# ADC_Block.net
KiCad netlist of a schematic drawn in EAGLE
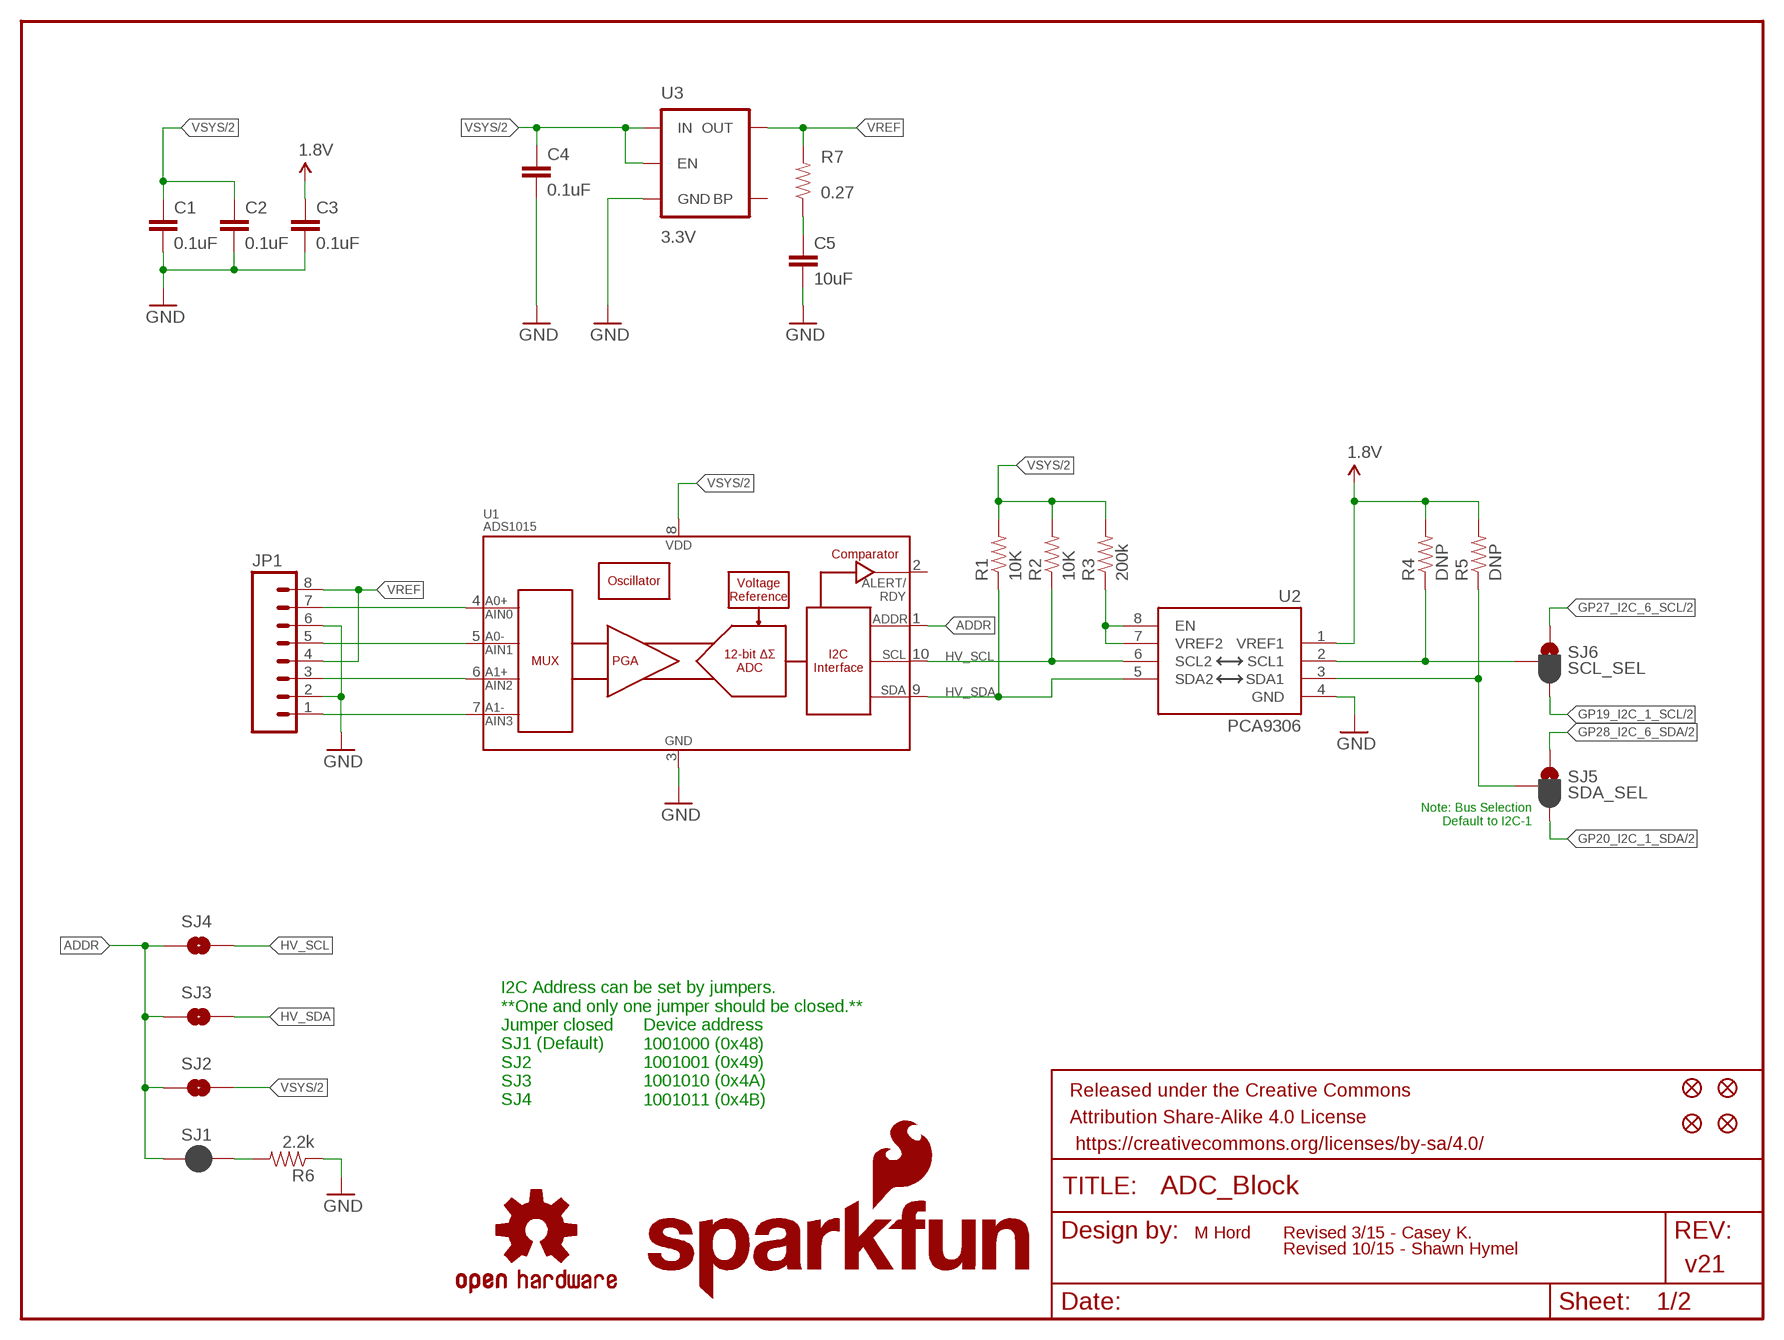
[diagram p0: schematic, sheet 1]
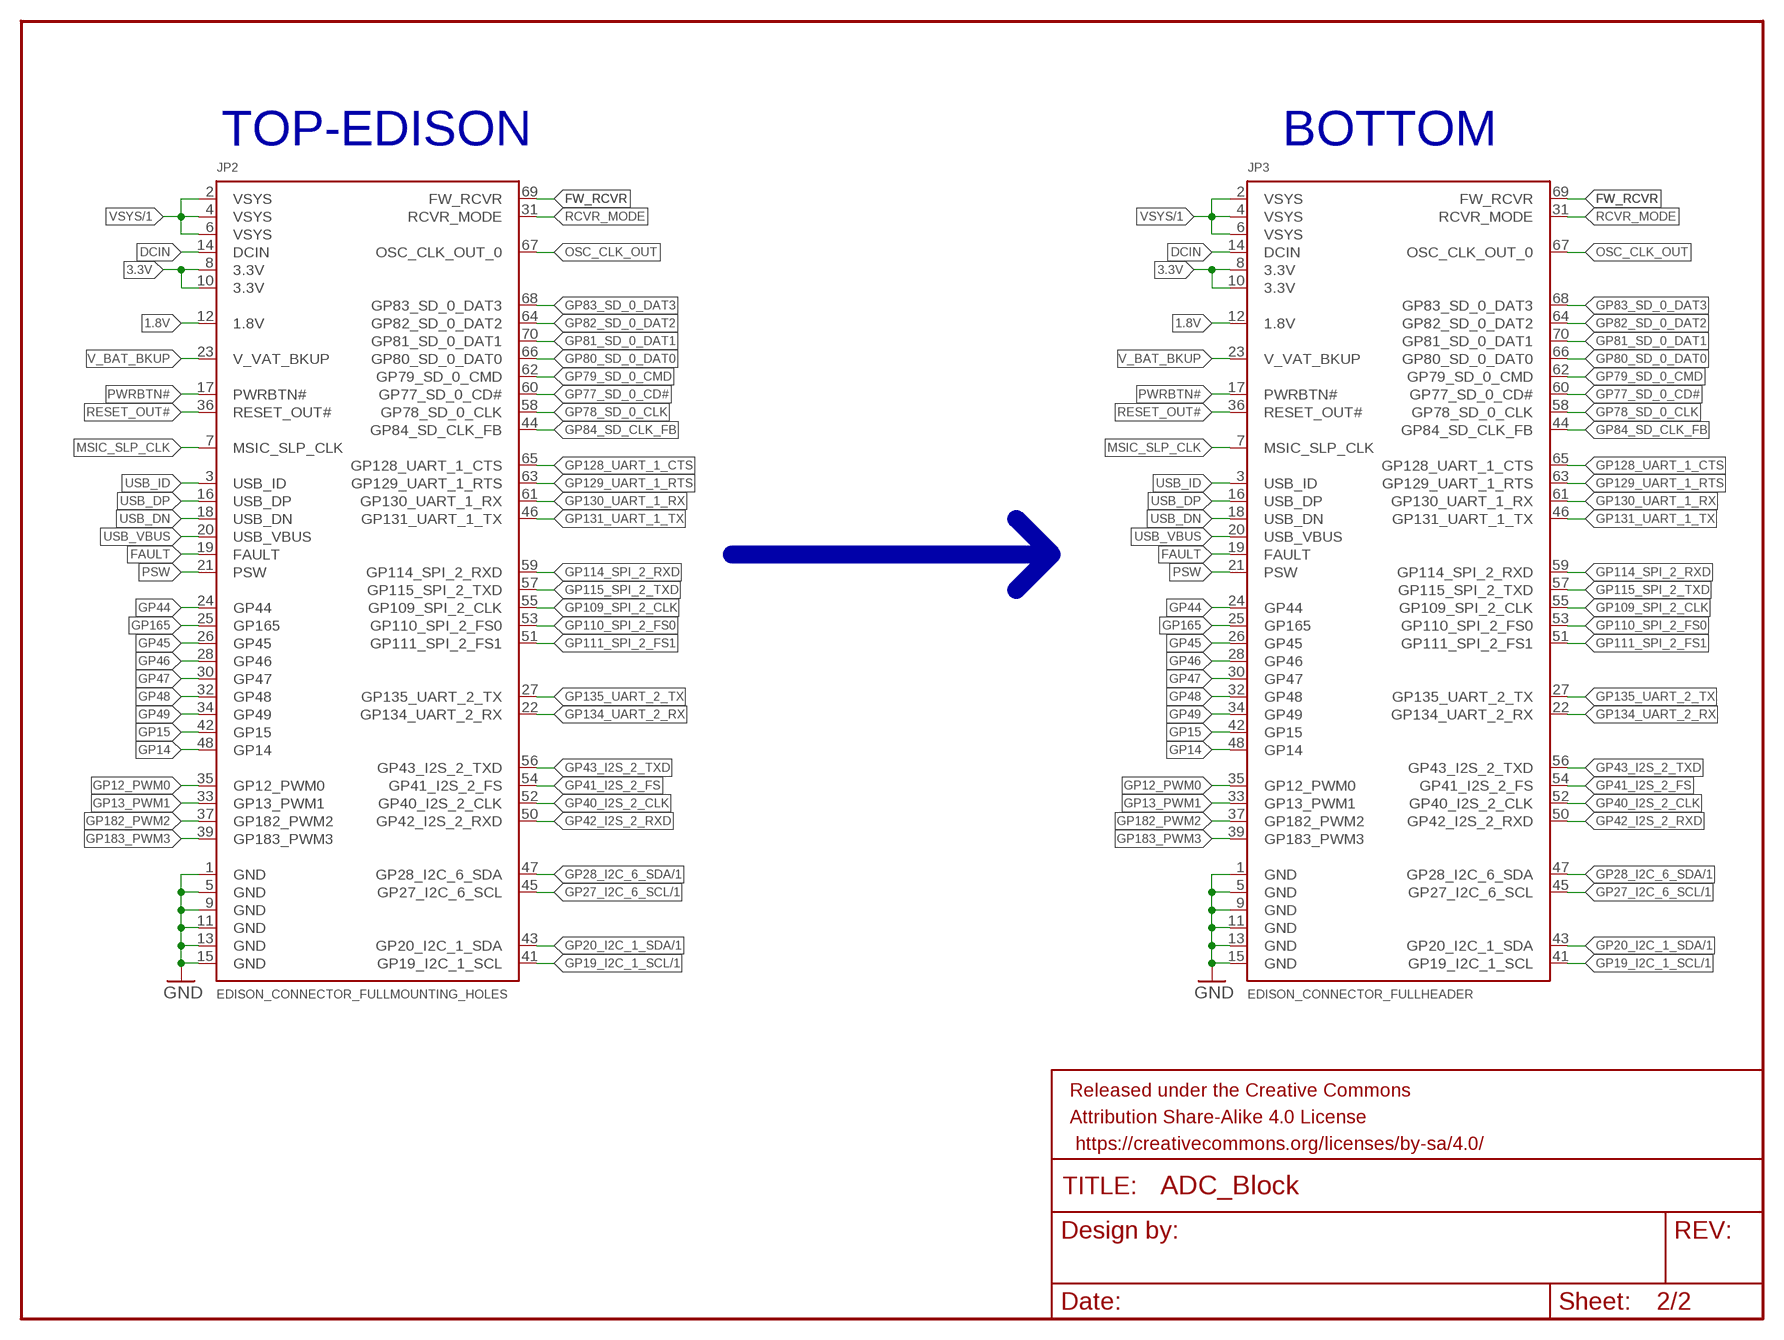
[diagram p1: schematic, sheet 2]

(export (version "E")
  (design (tool "Eeschema 10.0.6"))
  (components
    (comp (ref "C1")
      (value "0.1uF")
      (footprint "eagle-import:0603-CAP")
      (libsource (lib "eagle-import") (part "0.1UF-25V(+80/-20%)(0603)"))
    )
    (comp (ref "C2")
      (value "0.1uF")
      (footprint "eagle-import:0603-CAP")
      (libsource (lib "eagle-import") (part "0.1UF-25V(+80/-20%)(0603)"))
    )
    (comp (ref "C3")
      (value "0.1uF")
      (footprint "eagle-import:0603-CAP")
      (libsource (lib "eagle-import") (part "0.1UF-25V(+80/-20%)(0603)"))
    )
    (comp (ref "C4")
      (value "0.1uF")
      (footprint "eagle-import:0603-CAP")
      (libsource (lib "eagle-import") (part "0.1UF-25V(+80/-20%)(0603)"))
    )
    (comp (ref "C5")
      (value "10uF")
      (footprint "eagle-import:0805-CAP")
      (libsource (lib "eagle-import") (part "10UF10V10%(0805)"))
    )
    (comp (ref "FID1")
      (value "FIDUCIAL1X2")
      (footprint "eagle-import:FIDUCIAL-1X2")
      (libsource (lib "eagle-import") (part "FIDUCIAL1X2"))
    )
    (comp (ref "FID2")
      (value "FIDUCIAL1X2")
      (footprint "eagle-import:FIDUCIAL-1X2")
      (libsource (lib "eagle-import") (part "FIDUCIAL1X2"))
    )
    (comp (ref "FID3")
      (value "FIDUCIAL1X2")
      (footprint "eagle-import:FIDUCIAL-1X2")
      (libsource (lib "eagle-import") (part "FIDUCIAL1X2"))
    )
    (comp (ref "FID4")
      (value "FIDUCIAL1X2")
      (footprint "eagle-import:FIDUCIAL-1X2")
      (libsource (lib "eagle-import") (part "FIDUCIAL1X2"))
    )
    (comp (ref "FRAME1")
      (value "FRAME-LETTER")
      (footprint "eagle-import:CREATIVE_COMMONS")
      (libsource (lib "eagle-import") (part "FRAME-LETTER"))
    )
    (comp (ref "JP1")
      (value "M08LOCK")
      (footprint "eagle-import:1X08_LOCK")
      (libsource (lib "eagle-import") (part "M08LOCK"))
    )
    (comp (ref "LOGO1")
      (value "SFE_LOGO_NAME_FLAME.1_INCH")
      (footprint "eagle-import:SFE_LOGO_NAME_FLAME_.1")
      (libsource (lib "eagle-import") (part "SFE_LOGO_NAME_FLAME.1_INCH"))
    )
    (comp (ref "LOGO2")
      (value "OSHW-LOGOS")
      (footprint "eagle-import:OSHW-LOGO-S")
      (libsource (lib "eagle-import") (part "OSHW-LOGOS"))
    )
    (comp (ref "LOGO3")
      (value "SFE_LOGO_NAME_FLAME.1_INCH")
      (footprint "eagle-import:SFE_LOGO_NAME_FLAME_.1")
      (libsource (lib "eagle-import") (part "SFE_LOGO_NAME_FLAME.1_INCH"))
    )
    (comp (ref "LOGO4")
      (value "OSHW-LOGOS")
      (footprint "eagle-import:OSHW-LOGO-S")
      (libsource (lib "eagle-import") (part "OSHW-LOGOS"))
    )
    (comp (ref "R1")
      (value "10K")
      (footprint "eagle-import:0603-RES")
      (libsource (lib "eagle-import") (part "10KOHM-1/10W-1%(0603)0603"))
    )
    (comp (ref "R2")
      (value "10K")
      (footprint "eagle-import:0603-RES")
      (libsource (lib "eagle-import") (part "10KOHM-1/10W-1%(0603)0603"))
    )
    (comp (ref "R3")
      (value "200k")
      (footprint "eagle-import:0603-RES")
      (libsource (lib "eagle-import") (part "200KOHM1/10W1%(0603)200K"))
    )
    (comp (ref "R4")
      (value "DNP")
      (footprint "eagle-import:0603-RES")
      (libsource (lib "eagle-import") (part "2.2KOHM-1/10W-1%(0603)"))
    )
    (comp (ref "R5")
      (value "DNP")
      (footprint "eagle-import:0603-RES")
      (libsource (lib "eagle-import") (part "2.2KOHM-1/10W-1%(0603)"))
    )
    (comp (ref "R6")
      (value "2.2k")
      (footprint "eagle-import:0603-RES")
      (libsource (lib "eagle-import") (part "2.2KOHM-1/10W-1%(0603)"))
    )
    (comp (ref "R7")
      (value "0.27")
      (footprint "eagle-import:0603-RES")
      (libsource (lib "eagle-import") (part "0.27OHM-1/10W-1%(0603)"))
    )
    (comp (ref "SJ1")
      (value "JUMPER-PAD-2-NC_BY_PASTE")
      (footprint "eagle-import:PAD-JUMPER-2-NC_BY_PASTE_YES_SILK")
      (libsource (lib "eagle-import") (part "JUMPER-PAD-2-NC_BY_PASTE"))
    )
    (comp (ref "SJ2")
      (value "JUMPER-PAD-2-NOYES_SILK")
      (footprint "eagle-import:PAD-JUMPER-2-NO_YES_SILK")
      (libsource (lib "eagle-import") (part "JUMPER-PAD-2-NOYES_SILK"))
    )
    (comp (ref "SJ3")
      (value "JUMPER-PAD-2-NOYES_SILK")
      (footprint "eagle-import:PAD-JUMPER-2-NO_YES_SILK")
      (libsource (lib "eagle-import") (part "JUMPER-PAD-2-NOYES_SILK"))
    )
    (comp (ref "SJ4")
      (value "JUMPER-PAD-2-NOYES_SILK")
      (footprint "eagle-import:PAD-JUMPER-2-NO_YES_SILK")
      (libsource (lib "eagle-import") (part "JUMPER-PAD-2-NOYES_SILK"))
    )
    (comp (ref "SJ5")
      (value "SDA_SEL")
      (footprint "eagle-import:PAD-JUMPER-3-2OF3_NC_BY_PASTE_YES_SILK_FULL_BOX")
      (libsource (lib "eagle-import") (part "JUMPER-PAD-3-2OF3_NC_BY_PASTE"))
    )
    (comp (ref "SJ6")
      (value "SCL_SEL")
      (footprint "eagle-import:PAD-JUMPER-3-2OF3_NC_BY_PASTE_YES_SILK_FULL_BOX")
      (libsource (lib "eagle-import") (part "JUMPER-PAD-3-2OF3_NC_BY_PASTE"))
    )
    (comp (ref "U1")
      (value "ADS1015")
      (footprint "eagle-import:MSOP10")
      (libsource (lib "eagle-import") (part "ADS1015"))
    )
    (comp (ref "U2")
      (value "PCA9306")
      (footprint "eagle-import:PCA9306DC-1_1")
      (libsource (lib "eagle-import") (part "PCA9306PCA9306DC-1{colon}1"))
    )
    (comp (ref "U3")
      (value "3.3V")
      (footprint "eagle-import:SOT23-5")
      (libsource (lib "eagle-import") (part "MIC52053.3V"))
    )
    (comp (ref "FRAME2")
      (value "FRAME-LETTER")
      (footprint "eagle-import:CREATIVE_COMMONS")
      (libsource (lib "eagle-import") (part "FRAME-LETTER"))
    )
    (comp (ref "JP2")
      (value "EDISON_CONNECTOR_FULLMOUNTING_HOLES")
      (footprint "eagle-import:EDISON_DAUGHTER")
      (libsource (lib "eagle-import") (part "EDISON_CONNECTOR_FULLMOUNTING_HOLES"))
    )
    (comp (ref "JP3")
      (value "EDISON_CONNECTOR_FULLHEADER")
      (footprint "eagle-import:DF40C-70DP-0.4(51)")
      (libsource (lib "eagle-import") (part "EDISON_CONNECTOR_FULLHEADER"))
    )
  )
  (nets
    (net (code "1") (name "1.8V") (class "Default")
      (node (ref "C3") (pin "1") (pinfunction "1_1") (pintype "passive"))
      (node (ref "JP2") (pin "12") (pinfunction "1.8V_12") (pintype "bidirectional"))
      (node (ref "JP3") (pin "12") (pinfunction "1.8V_12") (pintype "bidirectional"))
      (node (ref "R4") (pin "2") (pinfunction "2_2") (pintype "passive"))
      (node (ref "R5") (pin "2") (pinfunction "2_2") (pintype "passive"))
      (node (ref "U2") (pin "1") (pinfunction "VREF1_1") (pintype "bidirectional"))
    )
    (net (code "2") (name "3.3V") (class "Default")
      (node (ref "JP2") (pin "10") (pinfunction "3.3V_10") (pintype "bidirectional"))
      (node (ref "JP2") (pin "8") (pinfunction "3.3V_8") (pintype "bidirectional"))
      (node (ref "JP3") (pin "10") (pinfunction "3.3V_10") (pintype "bidirectional"))
      (node (ref "JP3") (pin "8") (pinfunction "3.3V_8") (pintype "bidirectional"))
    )
    (net (code "3") (name "ADDR") (class "Default")
      (node (ref "SJ1") (pin "1") (pinfunction "1_1") (pintype "passive"))
      (node (ref "SJ2") (pin "1") (pinfunction "1_1") (pintype "passive"))
      (node (ref "SJ3") (pin "1") (pinfunction "1_1") (pintype "passive"))
      (node (ref "SJ4") (pin "1") (pinfunction "1_1") (pintype "passive"))
      (node (ref "U1") (pin "1") (pinfunction "ADDR_1") (pintype "bidirectional"))
    )
    (net (code "4") (name "DCIN") (class "Default")
      (node (ref "JP2") (pin "14") (pinfunction "DCIN_14") (pintype "bidirectional"))
      (node (ref "JP3") (pin "14") (pinfunction "DCIN_14") (pintype "bidirectional"))
    )
    (net (code "5") (name "FAULT") (class "Default")
      (node (ref "JP2") (pin "19") (pinfunction "FAULT_19") (pintype "bidirectional"))
      (node (ref "JP3") (pin "19") (pinfunction "FAULT_19") (pintype "bidirectional"))
    )
    (net (code "6") (name "FW_RCVR") (class "Default")
      (node (ref "JP2") (pin "69") (pinfunction "FW_RCVR_69") (pintype "bidirectional"))
      (node (ref "JP3") (pin "69") (pinfunction "FW_RCVR_69") (pintype "bidirectional"))
    )
    (net (code "7") (name "GND") (class "Default")
      (node (ref "C1") (pin "2") (pinfunction "2_2") (pintype "passive"))
      (node (ref "C2") (pin "2") (pinfunction "2_2") (pintype "passive"))
      (node (ref "C3") (pin "2") (pinfunction "2_2") (pintype "passive"))
      (node (ref "C4") (pin "2") (pinfunction "2_2") (pintype "passive"))
      (node (ref "C5") (pin "2") (pinfunction "2_2") (pintype "passive"))
      (node (ref "JP1") (pin "2") (pinfunction "2_2") (pintype "passive"))
      (node (ref "JP1") (pin "6") (pinfunction "6_6") (pintype "passive"))
      (node (ref "JP2") (pin "1") (pinfunction "GND_1") (pintype "bidirectional"))
      (node (ref "JP2") (pin "11") (pinfunction "GND_11") (pintype "bidirectional"))
      (node (ref "JP2") (pin "13") (pinfunction "GND_13") (pintype "bidirectional"))
      (node (ref "JP2") (pin "15") (pinfunction "GND_15") (pintype "bidirectional"))
      (node (ref "JP2") (pin "5") (pinfunction "GND_5") (pintype "bidirectional"))
      (node (ref "JP2") (pin "9") (pinfunction "GND_9") (pintype "bidirectional"))
      (node (ref "JP3") (pin "1") (pinfunction "GND_1") (pintype "bidirectional"))
      (node (ref "JP3") (pin "11") (pinfunction "GND_11") (pintype "bidirectional"))
      (node (ref "JP3") (pin "13") (pinfunction "GND_13") (pintype "bidirectional"))
      (node (ref "JP3") (pin "15") (pinfunction "GND_15") (pintype "bidirectional"))
      (node (ref "JP3") (pin "5") (pinfunction "GND_5") (pintype "bidirectional"))
      (node (ref "JP3") (pin "9") (pinfunction "GND_9") (pintype "bidirectional"))
      (node (ref "R6") (pin "1") (pinfunction "1_1") (pintype "passive"))
      (node (ref "U1") (pin "3") (pinfunction "VSS_3") (pintype "bidirectional"))
      (node (ref "U2") (pin "4") (pinfunction "GND_4") (pintype "bidirectional"))
      (node (ref "U3") (pin "2") (pinfunction "GND_2") (pintype "input"))
    )
    (net (code "8") (name "GP12_PWM0") (class "Default")
      (node (ref "JP2") (pin "35") (pinfunction "GP12_PWM0_35") (pintype "bidirectional"))
      (node (ref "JP3") (pin "35") (pinfunction "GP12_PWM0_35") (pintype "bidirectional"))
    )
    (net (code "9") (name "GP13_PWM1") (class "Default")
      (node (ref "JP2") (pin "33") (pinfunction "GP13_PWM1_33") (pintype "bidirectional"))
      (node (ref "JP3") (pin "33") (pinfunction "GP13_PWM1_33") (pintype "bidirectional"))
    )
    (net (code "10") (name "GP14") (class "Default")
      (node (ref "JP2") (pin "48") (pinfunction "GP14_48") (pintype "bidirectional"))
      (node (ref "JP3") (pin "48") (pinfunction "GP14_48") (pintype "bidirectional"))
    )
    (net (code "11") (name "GP15") (class "Default")
      (node (ref "JP2") (pin "42") (pinfunction "GP15_42") (pintype "bidirectional"))
      (node (ref "JP3") (pin "42") (pinfunction "GP15_42") (pintype "bidirectional"))
    )
    (net (code "12") (name "GP19_I2C_1_SCL") (class "Default")
      (node (ref "JP2") (pin "41") (pinfunction "GP19_I2C_1_SCL_41") (pintype "bidirectional"))
      (node (ref "JP3") (pin "41") (pinfunction "GP19_I2C_1_SCL_41") (pintype "bidirectional"))
      (node (ref "SJ6") (pin "3") (pinfunction "3_3") (pintype "passive"))
    )
    (net (code "13") (name "GP20_I2C_1_SDA") (class "Default")
      (node (ref "JP2") (pin "43") (pinfunction "GP20_I2C_1_SDA_43") (pintype "bidirectional"))
      (node (ref "JP3") (pin "43") (pinfunction "GP20_I2C_1_SDA_43") (pintype "bidirectional"))
      (node (ref "SJ5") (pin "3") (pinfunction "3_3") (pintype "passive"))
    )
    (net (code "14") (name "GP27_I2C_6_SCL") (class "Default")
      (node (ref "JP2") (pin "45") (pinfunction "GP27_I2C_6_SCL_45") (pintype "bidirectional"))
      (node (ref "JP3") (pin "45") (pinfunction "GP27_I2C_6_SCL_45") (pintype "bidirectional"))
      (node (ref "SJ6") (pin "1") (pinfunction "1_1") (pintype "passive"))
    )
    (net (code "15") (name "GP28_I2C_6_SDA") (class "Default")
      (node (ref "JP2") (pin "47") (pinfunction "GP28_I2C_6_SDA_47") (pintype "bidirectional"))
      (node (ref "JP3") (pin "47") (pinfunction "GP28_I2C_6_SDA_47") (pintype "bidirectional"))
      (node (ref "SJ5") (pin "1") (pinfunction "1_1") (pintype "passive"))
    )
    (net (code "16") (name "GP40_I2S_2_CLK") (class "Default")
      (node (ref "JP2") (pin "52") (pinfunction "GP40_I2S_2_CLK_52") (pintype "bidirectional"))
      (node (ref "JP3") (pin "52") (pinfunction "GP40_I2S_2_CLK_52") (pintype "bidirectional"))
    )
    (net (code "17") (name "GP41_I2S_2_FS") (class "Default")
      (node (ref "JP2") (pin "54") (pinfunction "GP41_I2S_2_FS_54") (pintype "bidirectional"))
      (node (ref "JP3") (pin "54") (pinfunction "GP41_I2S_2_FS_54") (pintype "bidirectional"))
    )
    (net (code "18") (name "GP42_I2S_2_RXD") (class "Default")
      (node (ref "JP2") (pin "50") (pinfunction "GP42_I2S_2_RXD_50") (pintype "bidirectional"))
      (node (ref "JP3") (pin "50") (pinfunction "GP42_I2S_2_RXD_50") (pintype "bidirectional"))
    )
    (net (code "19") (name "GP43_I2S_2_TXD") (class "Default")
      (node (ref "JP2") (pin "56") (pinfunction "GP43_I2S_2_TXD_56") (pintype "bidirectional"))
      (node (ref "JP3") (pin "56") (pinfunction "GP43_I2S_2_TXD_56") (pintype "bidirectional"))
    )
    (net (code "20") (name "GP44") (class "Default")
      (node (ref "JP2") (pin "24") (pinfunction "GP44_24") (pintype "bidirectional"))
      (node (ref "JP3") (pin "24") (pinfunction "GP44_24") (pintype "bidirectional"))
    )
    (net (code "21") (name "GP45") (class "Default")
      (node (ref "JP2") (pin "26") (pinfunction "GP45_26") (pintype "bidirectional"))
      (node (ref "JP3") (pin "26") (pinfunction "GP45_26") (pintype "bidirectional"))
    )
    (net (code "22") (name "GP46") (class "Default")
      (node (ref "JP2") (pin "28") (pinfunction "GP46_28") (pintype "bidirectional"))
      (node (ref "JP3") (pin "28") (pinfunction "GP46_28") (pintype "bidirectional"))
    )
    (net (code "23") (name "GP47") (class "Default")
      (node (ref "JP2") (pin "30") (pinfunction "GP47_30") (pintype "bidirectional"))
      (node (ref "JP3") (pin "30") (pinfunction "GP47_30") (pintype "bidirectional"))
    )
    (net (code "24") (name "GP48") (class "Default")
      (node (ref "JP2") (pin "32") (pinfunction "GP48_32") (pintype "bidirectional"))
      (node (ref "JP3") (pin "32") (pinfunction "GP48_32") (pintype "bidirectional"))
    )
    (net (code "25") (name "GP49") (class "Default")
      (node (ref "JP2") (pin "34") (pinfunction "GP49_34") (pintype "bidirectional"))
      (node (ref "JP3") (pin "34") (pinfunction "GP49_34") (pintype "bidirectional"))
    )
    (net (code "26") (name "GP77_SD_0_CD#") (class "Default")
      (node (ref "JP2") (pin "60") (pinfunction "GP77_SD_0_CD#_60") (pintype "bidirectional"))
      (node (ref "JP3") (pin "60") (pinfunction "GP77_SD_0_CD#_60") (pintype "bidirectional"))
    )
    (net (code "27") (name "GP78_SD_0_CLK") (class "Default")
      (node (ref "JP2") (pin "58") (pinfunction "GP78_SD_0_CLK_58") (pintype "bidirectional"))
      (node (ref "JP3") (pin "58") (pinfunction "GP78_SD_0_CLK_58") (pintype "bidirectional"))
    )
    (net (code "28") (name "GP79_SD_0_CMD") (class "Default")
      (node (ref "JP2") (pin "62") (pinfunction "GP79_SD_0_CMD_62") (pintype "bidirectional"))
      (node (ref "JP3") (pin "62") (pinfunction "GP79_SD_0_CMD_62") (pintype "bidirectional"))
    )
    (net (code "29") (name "GP80_SD_0_DAT0") (class "Default")
      (node (ref "JP2") (pin "66") (pinfunction "GP80_SD_0_DAT0_66") (pintype "bidirectional"))
      (node (ref "JP3") (pin "66") (pinfunction "GP80_SD_0_DAT0_66") (pintype "bidirectional"))
    )
    (net (code "30") (name "GP81_SD_0_DAT1") (class "Default")
      (node (ref "JP2") (pin "70") (pinfunction "GP81_SD_0_DAT1_70") (pintype "bidirectional"))
      (node (ref "JP3") (pin "70") (pinfunction "GP81_SD_0_DAT1_70") (pintype "bidirectional"))
    )
    (net (code "31") (name "GP82_SD_0_DAT2") (class "Default")
      (node (ref "JP2") (pin "64") (pinfunction "GP82_SD_0_DAT2_64") (pintype "bidirectional"))
      (node (ref "JP3") (pin "64") (pinfunction "GP82_SD_0_DAT2_64") (pintype "bidirectional"))
    )
    (net (code "32") (name "GP83_SD_0_DAT3") (class "Default")
      (node (ref "JP2") (pin "68") (pinfunction "GP83_SD_0_DAT3_68") (pintype "bidirectional"))
      (node (ref "JP3") (pin "68") (pinfunction "GP83_SD_0_DAT3_68") (pintype "bidirectional"))
    )
    (net (code "33") (name "GP84_SD_CLK_FB") (class "Default")
      (node (ref "JP2") (pin "44") (pinfunction "GP84_SD_CLK_FB_44") (pintype "bidirectional"))
      (node (ref "JP3") (pin "44") (pinfunction "GP84_SD_CLK_FB_44") (pintype "bidirectional"))
    )
    (net (code "34") (name "GP109_SPI_2_CLK") (class "Default")
      (node (ref "JP2") (pin "55") (pinfunction "GP109_SPI_2_CLK_55") (pintype "bidirectional"))
      (node (ref "JP3") (pin "55") (pinfunction "GP109_SPI_2_CLK_55") (pintype "bidirectional"))
    )
    (net (code "35") (name "GP110_SPI_2_FS0") (class "Default")
      (node (ref "JP2") (pin "53") (pinfunction "GP110_SPI_2_FS0_53") (pintype "bidirectional"))
      (node (ref "JP3") (pin "53") (pinfunction "GP110_SPI_2_FS0_53") (pintype "bidirectional"))
    )
    (net (code "36") (name "GP111_SPI_2_FS1") (class "Default")
      (node (ref "JP2") (pin "51") (pinfunction "GP111_SPI_2_FS1_51") (pintype "bidirectional"))
      (node (ref "JP3") (pin "51") (pinfunction "GP111_SPI_2_FS1_51") (pintype "bidirectional"))
    )
    (net (code "37") (name "GP114_SPI_2_RXD") (class "Default")
      (node (ref "JP2") (pin "59") (pinfunction "GP114_SPI_2_RXD_59") (pintype "bidirectional"))
      (node (ref "JP3") (pin "59") (pinfunction "GP114_SPI_2_RXD_59") (pintype "bidirectional"))
    )
    (net (code "38") (name "GP115_SPI_2_TXD") (class "Default")
      (node (ref "JP2") (pin "57") (pinfunction "GP115_SPI_2_TXD_57") (pintype "bidirectional"))
      (node (ref "JP3") (pin "57") (pinfunction "GP115_SPI_2_TXD_57") (pintype "bidirectional"))
    )
    (net (code "39") (name "GP128_UART_1_CTS") (class "Default")
      (node (ref "JP2") (pin "65") (pinfunction "GP128_UART_1_CTS_65") (pintype "bidirectional"))
      (node (ref "JP3") (pin "65") (pinfunction "GP128_UART_1_CTS_65") (pintype "bidirectional"))
    )
    (net (code "40") (name "GP129_UART_1_RTS") (class "Default")
      (node (ref "JP2") (pin "63") (pinfunction "GP129_UART_1_RTS_63") (pintype "bidirectional"))
      (node (ref "JP3") (pin "63") (pinfunction "GP129_UART_1_RTS_63") (pintype "bidirectional"))
    )
    (net (code "41") (name "GP130_UART_1_RX") (class "Default")
      (node (ref "JP2") (pin "61") (pinfunction "GP130_UART_1_RX_61") (pintype "bidirectional"))
      (node (ref "JP3") (pin "61") (pinfunction "GP130_UART_1_RX_61") (pintype "bidirectional"))
    )
    (net (code "42") (name "GP131_UART_1_TX") (class "Default")
      (node (ref "JP2") (pin "46") (pinfunction "GP131_UART_1_TX_46") (pintype "bidirectional"))
      (node (ref "JP3") (pin "46") (pinfunction "GP131_UART_1_TX_46") (pintype "bidirectional"))
    )
    (net (code "43") (name "GP134_UART_2_RX") (class "Default")
      (node (ref "JP2") (pin "22") (pinfunction "GP134_UART_2_RX_22") (pintype "bidirectional"))
      (node (ref "JP3") (pin "22") (pinfunction "GP134_UART_2_RX_22") (pintype "bidirectional"))
    )
    (net (code "44") (name "GP135_UART_2_TX") (class "Default")
      (node (ref "JP2") (pin "27") (pinfunction "GP135_UART_2_TX_27") (pintype "bidirectional"))
      (node (ref "JP3") (pin "27") (pinfunction "GP135_UART_2_TX_27") (pintype "bidirectional"))
    )
    (net (code "45") (name "GP165") (class "Default")
      (node (ref "JP2") (pin "25") (pinfunction "GP165_25") (pintype "bidirectional"))
      (node (ref "JP3") (pin "25") (pinfunction "GP165_25") (pintype "bidirectional"))
    )
    (net (code "46") (name "GP182_PWM2") (class "Default")
      (node (ref "JP2") (pin "37") (pinfunction "GP182_PWM2_37") (pintype "bidirectional"))
      (node (ref "JP3") (pin "37") (pinfunction "GP182_PWM2_37") (pintype "bidirectional"))
    )
    (net (code "47") (name "GP183_PWM3") (class "Default")
      (node (ref "JP2") (pin "39") (pinfunction "GP183_PWM3_39") (pintype "bidirectional"))
      (node (ref "JP3") (pin "39") (pinfunction "GP183_PWM3_39") (pintype "bidirectional"))
    )
    (net (code "48") (name "HV_SCL") (class "Default")
      (node (ref "R2") (pin "1") (pinfunction "1_1") (pintype "passive"))
      (node (ref "SJ4") (pin "2") (pinfunction "2_2") (pintype "passive"))
      (node (ref "U1") (pin "10") (pinfunction "SCL_10") (pintype "bidirectional"))
      (node (ref "U2") (pin "6") (pinfunction "SCL2_6") (pintype "bidirectional"))
    )
    (net (code "49") (name "HV_SDA") (class "Default")
      (node (ref "R1") (pin "1") (pinfunction "1_1") (pintype "passive"))
      (node (ref "SJ3") (pin "2") (pinfunction "2_2") (pintype "passive"))
      (node (ref "U1") (pin "9") (pinfunction "SDA_9") (pintype "bidirectional"))
      (node (ref "U2") (pin "5") (pinfunction "SDA2_5") (pintype "bidirectional"))
    )
    (net (code "50") (name "MSIC_SLP_CLK") (class "Default")
      (node (ref "JP2") (pin "7") (pinfunction "MSIC_SLP_CLK_7") (pintype "bidirectional"))
      (node (ref "JP3") (pin "7") (pinfunction "MSIC_SLP_CLK_7") (pintype "bidirectional"))
    )
    (net (code "51") (name "Net-(C5-Pad1)") (class "Default")
      (node (ref "C5") (pin "1") (pinfunction "1_1") (pintype "passive"))
      (node (ref "R7") (pin "1") (pinfunction "1_1") (pintype "passive"))
    )
    (net (code "52") (name "Net-(R6-Pad2)") (class "Default")
      (node (ref "R6") (pin "2") (pinfunction "2_2") (pintype "passive"))
      (node (ref "SJ1") (pin "2") (pinfunction "2_2") (pintype "passive"))
    )
    (net (code "53") (name "Net-(U1-AIN0)") (class "Default")
      (node (ref "JP1") (pin "7") (pinfunction "7_7") (pintype "passive"))
      (node (ref "U1") (pin "4") (pinfunction "AIN0_4") (pintype "bidirectional"))
    )
    (net (code "54") (name "Net-(U1-AIN1)") (class "Default")
      (node (ref "JP1") (pin "5") (pinfunction "5_5") (pintype "passive"))
      (node (ref "U1") (pin "5") (pinfunction "AIN1_5") (pintype "bidirectional"))
    )
    (net (code "55") (name "Net-(U1-AIN2)") (class "Default")
      (node (ref "JP1") (pin "3") (pinfunction "3_3") (pintype "passive"))
      (node (ref "U1") (pin "6") (pinfunction "AIN2_6") (pintype "bidirectional"))
    )
    (net (code "56") (name "Net-(U1-AIN3)") (class "Default")
      (node (ref "JP1") (pin "1") (pinfunction "1_1") (pintype "passive"))
      (node (ref "U1") (pin "7") (pinfunction "AIN3_7") (pintype "bidirectional"))
    )
    (net (code "57") (name "Net-(U2-EN)") (class "Default")
      (node (ref "R3") (pin "1") (pinfunction "1_1") (pintype "passive"))
      (node (ref "U2") (pin "7") (pinfunction "VREF2_7") (pintype "bidirectional"))
      (node (ref "U2") (pin "8") (pinfunction "EN_8") (pintype "bidirectional"))
    )
    (net (code "58") (name "Net-(U2-SCL1)") (class "Default")
      (node (ref "R4") (pin "1") (pinfunction "1_1") (pintype "passive"))
      (node (ref "SJ6") (pin "2") (pinfunction "2_2") (pintype "passive"))
      (node (ref "U2") (pin "2") (pinfunction "SCL1_2") (pintype "bidirectional"))
    )
    (net (code "59") (name "Net-(U2-SDA1)") (class "Default")
      (node (ref "R5") (pin "1") (pinfunction "1_1") (pintype "passive"))
      (node (ref "SJ5") (pin "2") (pinfunction "2_2") (pintype "passive"))
      (node (ref "U2") (pin "3") (pinfunction "SDA1_3") (pintype "bidirectional"))
    )
    (net (code "60") (name "OSC_CLK_OUT") (class "Default")
      (node (ref "JP2") (pin "67") (pinfunction "OSC_CLK_OUT_0_67") (pintype "bidirectional"))
      (node (ref "JP3") (pin "67") (pinfunction "OSC_CLK_OUT_0_67") (pintype "bidirectional"))
    )
    (net (code "61") (name "PSW") (class "Default")
      (node (ref "JP2") (pin "21") (pinfunction "PSW_21") (pintype "bidirectional"))
      (node (ref "JP3") (pin "21") (pinfunction "PSW_21") (pintype "bidirectional"))
    )
    (net (code "62") (name "PWRBTN#") (class "Default")
      (node (ref "JP2") (pin "17") (pinfunction "PWRBTN#_17") (pintype "bidirectional"))
      (node (ref "JP3") (pin "17") (pinfunction "PWRBTN#_17") (pintype "bidirectional"))
    )
    (net (code "63") (name "RCVR_MODE") (class "Default")
      (node (ref "JP2") (pin "31") (pinfunction "RCVR_MODE_31") (pintype "bidirectional"))
      (node (ref "JP3") (pin "31") (pinfunction "RCVR_MODE_31") (pintype "bidirectional"))
    )
    (net (code "64") (name "RESET_OUT#") (class "Default")
      (node (ref "JP2") (pin "36") (pinfunction "RESET_OUT#_36") (pintype "bidirectional"))
      (node (ref "JP3") (pin "36") (pinfunction "RESET_OUT#_36") (pintype "bidirectional"))
    )
    (net (code "65") (name "USB_DN") (class "Default")
      (node (ref "JP2") (pin "18") (pinfunction "USB_DN_18") (pintype "bidirectional"))
      (node (ref "JP3") (pin "18") (pinfunction "USB_DN_18") (pintype "bidirectional"))
    )
    (net (code "66") (name "USB_DP") (class "Default")
      (node (ref "JP2") (pin "16") (pinfunction "USB_DP_16") (pintype "bidirectional"))
      (node (ref "JP3") (pin "16") (pinfunction "USB_DP_16") (pintype "bidirectional"))
    )
    (net (code "67") (name "USB_ID") (class "Default")
      (node (ref "JP2") (pin "3") (pinfunction "USB_ID_3") (pintype "bidirectional"))
      (node (ref "JP3") (pin "3") (pinfunction "USB_ID_3") (pintype "bidirectional"))
    )
    (net (code "68") (name "USB_VBUS") (class "Default")
      (node (ref "JP2") (pin "20") (pinfunction "USB_VBUS_20") (pintype "bidirectional"))
      (node (ref "JP3") (pin "20") (pinfunction "USB_VBUS_20") (pintype "bidirectional"))
    )
    (net (code "69") (name "VREF") (class "Default")
      (node (ref "JP1") (pin "4") (pinfunction "4_4") (pintype "passive"))
      (node (ref "JP1") (pin "8") (pinfunction "8_8") (pintype "passive"))
      (node (ref "R7") (pin "2") (pinfunction "2_2") (pintype "passive"))
      (node (ref "U3") (pin "5") (pinfunction "OUT_5") (pintype "passive"))
    )
    (net (code "70") (name "VSYS") (class "Default")
      (node (ref "C1") (pin "1") (pinfunction "1_1") (pintype "passive"))
      (node (ref "C2") (pin "1") (pinfunction "1_1") (pintype "passive"))
      (node (ref "C4") (pin "1") (pinfunction "1_1") (pintype "passive"))
      (node (ref "JP2") (pin "2") (pinfunction "VSYS_2") (pintype "bidirectional"))
      (node (ref "JP2") (pin "4") (pinfunction "VSYS_4") (pintype "bidirectional"))
      (node (ref "JP2") (pin "6") (pinfunction "VSYS_6") (pintype "bidirectional"))
      (node (ref "JP3") (pin "2") (pinfunction "VSYS_2") (pintype "bidirectional"))
      (node (ref "JP3") (pin "4") (pinfunction "VSYS_4") (pintype "bidirectional"))
      (node (ref "JP3") (pin "6") (pinfunction "VSYS_6") (pintype "bidirectional"))
      (node (ref "R1") (pin "2") (pinfunction "2_2") (pintype "passive"))
      (node (ref "R2") (pin "2") (pinfunction "2_2") (pintype "passive"))
      (node (ref "R3") (pin "2") (pinfunction "2_2") (pintype "passive"))
      (node (ref "SJ2") (pin "2") (pinfunction "2_2") (pintype "passive"))
      (node (ref "U1") (pin "8") (pinfunction "VDD_8") (pintype "bidirectional"))
      (node (ref "U3") (pin "1") (pinfunction "IN_1") (pintype "input"))
      (node (ref "U3") (pin "3") (pinfunction "EN_3") (pintype "input"))
    )
    (net (code "71") (name "V_BAT_BKUP") (class "Default")
      (node (ref "JP2") (pin "23") (pinfunction "V_VAT_BKUP_23") (pintype "bidirectional"))
      (node (ref "JP3") (pin "23") (pinfunction "V_VAT_BKUP_23") (pintype "bidirectional"))
    )
    (net (code "72") (name "unconnected-(U1-ALERT{slash}RDY-Pad2)") (class "Default")
      (node (ref "U1") (pin "2") (pinfunction "ALERT/RDY_2") (pintype "bidirectional"))
    )
    (net (code "73") (name "unconnected-(U3-BP-Pad4)") (class "Default")
      (node (ref "U3") (pin "4") (pinfunction "BP_4") (pintype "input"))
    )
  )
)
